# Esquema.net
KiCad netlist of a schematic drawn in EAGLE
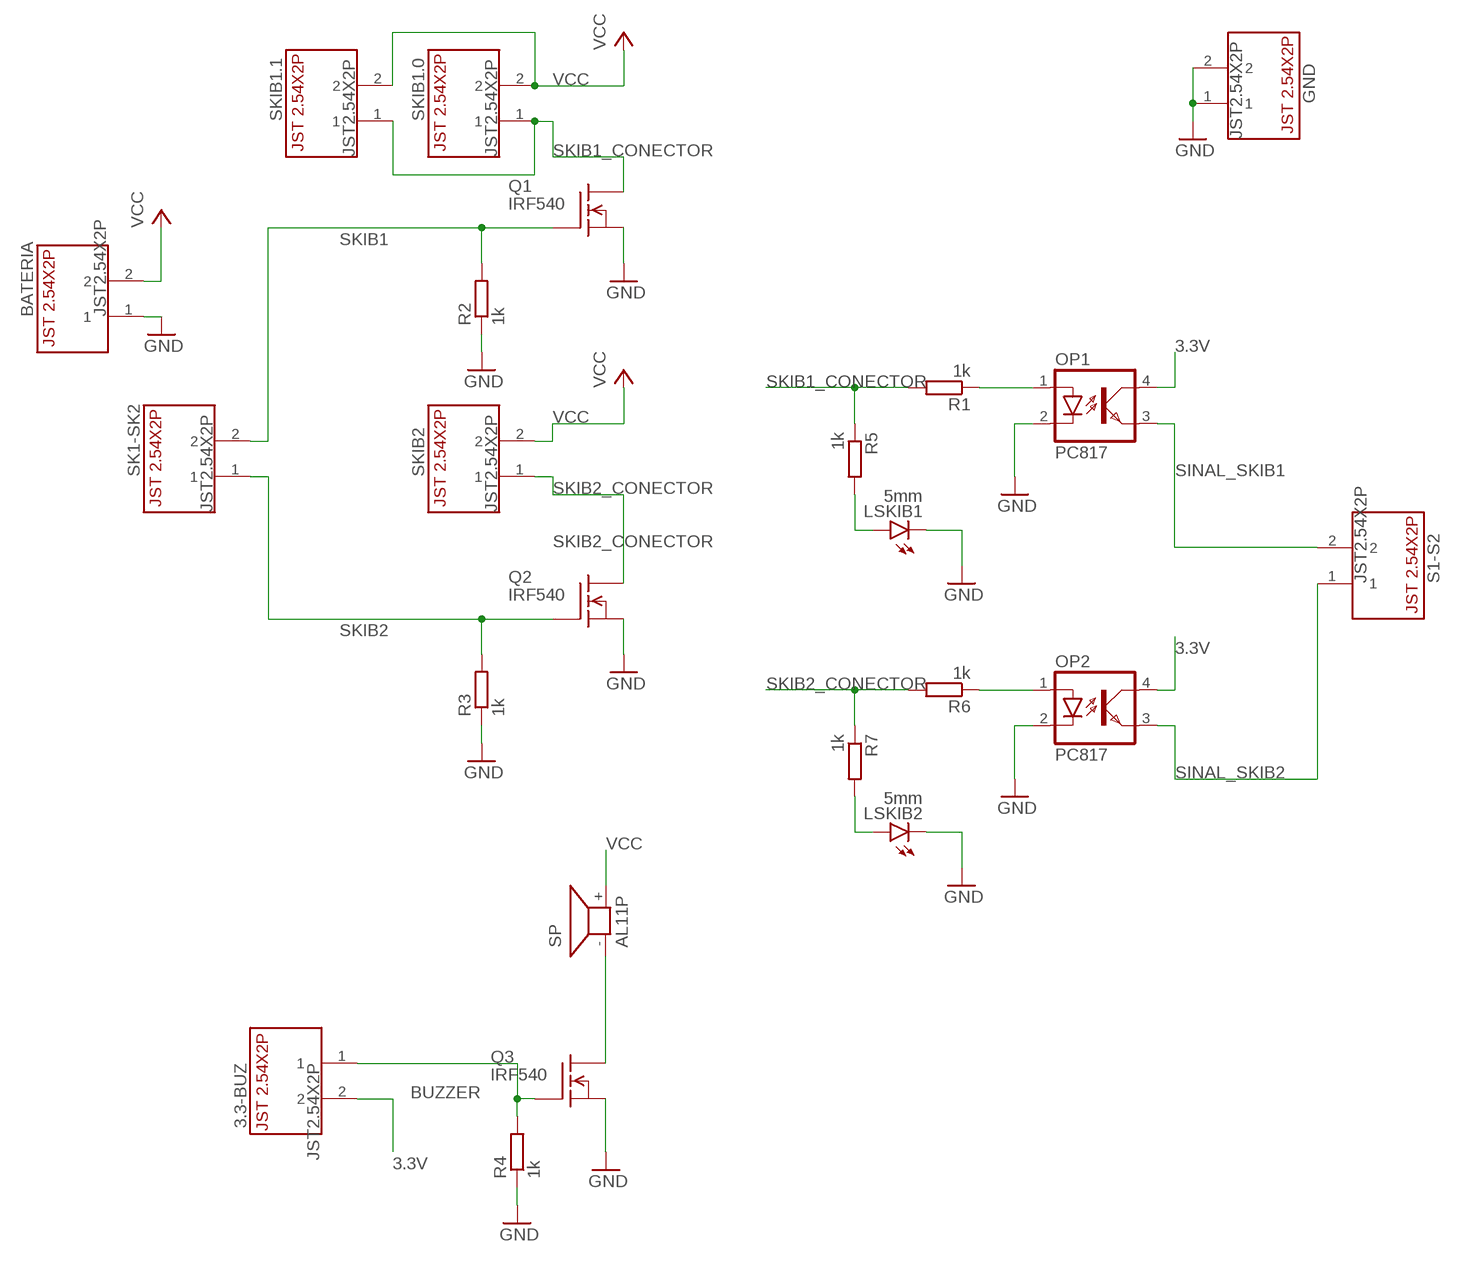
[diagram p0: schematic, sheet 1]

(export (version "E")
  (design (tool "Eeschema 10.0.6"))
  (components
    (comp (ref "3.3-BUZ")
      (value "JST2.54X2P")
      (footprint "eagle-import:JST2.54X2P_FOOTPRINT")
      (libsource (lib "eagle-import") (part "JST2.54X2P"))
    )
    (comp (ref "BATERIA")
      (value "JST2.54X2P")
      (footprint "eagle-import:JST2.54X2P_FOOTPRINT")
      (libsource (lib "eagle-import") (part "JST2.54X2P"))
    )
    (comp (ref "GND")
      (value "JST2.54X2P")
      (footprint "eagle-import:JST2.54X2P_FOOTPRINT")
      (libsource (lib "eagle-import") (part "JST2.54X2P"))
    )
    (comp (ref "LSKIB1")
      (value "5mm")
      (footprint "eagle-import:LED5MM")
      (libsource (lib "eagle-import") (part "LED5MM"))
    )
    (comp (ref "LSKIB2")
      (value "5mm")
      (footprint "eagle-import:LED5MM")
      (libsource (lib "eagle-import") (part "LED5MM"))
    )
    (comp (ref "OP1")
      (value "PC817")
      (footprint "eagle-import:DIL04")
      (fields (field (name "MPN") "PC817X4J000F"))
      (libsource (lib "eagle-import") (part "PC817"))
    )
    (comp (ref "OP2")
      (value "PC817")
      (footprint "eagle-import:DIL04")
      (fields (field (name "MPN") "PC817X4J000F"))
      (libsource (lib "eagle-import") (part "PC817"))
    )
    (comp (ref "Q1")
      (value "IRF540")
      (footprint "eagle-import:TO220")
      (libsource (lib "eagle-import") (part "IRF540"))
    )
    (comp (ref "Q2")
      (value "IRF540")
      (footprint "eagle-import:TO220")
      (libsource (lib "eagle-import") (part "IRF540"))
    )
    (comp (ref "Q3")
      (value "IRF540")
      (footprint "eagle-import:TO220")
      (libsource (lib "eagle-import") (part "IRF540"))
    )
    (comp (ref "R1")
      (value "1k")
      (footprint "eagle-import:0207_10")
      (libsource (lib "eagle-import") (part "R-EU_0207/10"))
    )
    (comp (ref "R2")
      (value "1k")
      (footprint "eagle-import:0207_10")
      (libsource (lib "eagle-import") (part "R-EU_0207/10"))
    )
    (comp (ref "R3")
      (value "1k")
      (footprint "eagle-import:0207_10")
      (libsource (lib "eagle-import") (part "R-EU_0207/10"))
    )
    (comp (ref "R4")
      (value "1k")
      (footprint "eagle-import:0207_10")
      (libsource (lib "eagle-import") (part "R-EU_0207/10"))
    )
    (comp (ref "R5")
      (value "1k")
      (footprint "eagle-import:0207_10")
      (libsource (lib "eagle-import") (part "R-EU_0207/10"))
    )
    (comp (ref "R6")
      (value "1k")
      (footprint "eagle-import:0207_10")
      (libsource (lib "eagle-import") (part "R-EU_0207/10"))
    )
    (comp (ref "R7")
      (value "1k")
      (footprint "eagle-import:0207_10")
      (libsource (lib "eagle-import") (part "R-EU_0207/10"))
    )
    (comp (ref "S1-S2")
      (value "JST2.54X2P")
      (footprint "eagle-import:JST2.54X2P_FOOTPRINT")
      (libsource (lib "eagle-import") (part "JST2.54X2P"))
    )
    (comp (ref "SK1-SK2")
      (value "JST2.54X2P")
      (footprint "eagle-import:JST2.54X2P_FOOTPRINT")
      (libsource (lib "eagle-import") (part "JST2.54X2P"))
    )
    (comp (ref "SKIB1.0")
      (value "JST2.54X2P")
      (footprint "eagle-import:JST2.54X2P_FOOTPRINT")
      (libsource (lib "eagle-import") (part "JST2.54X2P"))
    )
    (comp (ref "SKIB1.1")
      (value "JST2.54X2P")
      (footprint "eagle-import:JST2.54X2P_FOOTPRINT")
      (libsource (lib "eagle-import") (part "JST2.54X2P"))
    )
    (comp (ref "SKIB2")
      (value "JST2.54X2P")
      (footprint "eagle-import:JST2.54X2P_FOOTPRINT")
      (libsource (lib "eagle-import") (part "JST2.54X2P"))
    )
    (comp (ref "SP")
      (value "AL11P")
      (footprint "eagle-import:AL11P")
      (libsource (lib "eagle-import") (part "AL11P"))
    )
  )
  (nets
    (net (code "1") (name "/3.3V") (class "Default")
      (node (ref "3.3-BUZ") (pin "2") (pinfunction "2_2") (pintype "bidirectional"))
      (node (ref "OP1") (pin "4") (pinfunction "COL_4") (pintype "passive"))
      (node (ref "OP2") (pin "4") (pinfunction "COL_4") (pintype "passive"))
    )
    (net (code "2") (name "/BUZZER") (class "Default")
      (node (ref "3.3-BUZ") (pin "1") (pinfunction "1_1") (pintype "bidirectional"))
      (node (ref "Q3") (pin "1") (pinfunction "G_1") (pintype "passive"))
      (node (ref "R4") (pin "2") (pinfunction "2_2") (pintype "passive"))
    )
    (net (code "3") (name "/SINAL_SKIB1") (class "Default")
      (node (ref "OP1") (pin "3") (pinfunction "EMIT_3") (pintype "passive"))
      (node (ref "S1-S2") (pin "2") (pinfunction "2_2") (pintype "bidirectional"))
    )
    (net (code "4") (name "/SINAL_SKIB2") (class "Default")
      (node (ref "OP2") (pin "3") (pinfunction "EMIT_3") (pintype "passive"))
      (node (ref "S1-S2") (pin "1") (pinfunction "1_1") (pintype "bidirectional"))
    )
    (net (code "5") (name "/SKIB1") (class "Default")
      (node (ref "Q1") (pin "1") (pinfunction "G_1") (pintype "passive"))
      (node (ref "R2") (pin "2") (pinfunction "2_2") (pintype "passive"))
      (node (ref "SK1-SK2") (pin "2") (pinfunction "2_2") (pintype "bidirectional"))
    )
    (net (code "6") (name "/SKIB1_CONECTOR") (class "Default")
      (node (ref "Q1") (pin "2") (pinfunction "D_2") (pintype "passive"))
      (node (ref "R1") (pin "2") (pinfunction "2_2") (pintype "passive"))
      (node (ref "R5") (pin "1") (pinfunction "1_1") (pintype "passive"))
      (node (ref "SKIB1.0") (pin "1") (pinfunction "1_1") (pintype "bidirectional"))
      (node (ref "SKIB1.1") (pin "1") (pinfunction "1_1") (pintype "bidirectional"))
    )
    (net (code "7") (name "/SKIB2") (class "Default")
      (node (ref "Q2") (pin "1") (pinfunction "G_1") (pintype "passive"))
      (node (ref "R3") (pin "2") (pinfunction "2_2") (pintype "passive"))
      (node (ref "SK1-SK2") (pin "1") (pinfunction "1_1") (pintype "bidirectional"))
    )
    (net (code "8") (name "/SKIB2_CONECTOR") (class "Default")
      (node (ref "Q2") (pin "2") (pinfunction "D_2") (pintype "passive"))
      (node (ref "R6") (pin "2") (pinfunction "2_2") (pintype "passive"))
      (node (ref "R7") (pin "1") (pinfunction "1_1") (pintype "passive"))
      (node (ref "SKIB2") (pin "1") (pinfunction "1_1") (pintype "bidirectional"))
    )
    (net (code "9") (name "GND") (class "Default")
      (node (ref "BATERIA") (pin "1") (pinfunction "1_1") (pintype "bidirectional"))
      (node (ref "GND") (pin "1") (pinfunction "1_1") (pintype "bidirectional"))
      (node (ref "GND") (pin "2") (pinfunction "2_2") (pintype "bidirectional"))
      (node (ref "LSKIB1") (pin "K") (pinfunction "C_K") (pintype "passive"))
      (node (ref "LSKIB2") (pin "K") (pinfunction "C_K") (pintype "passive"))
      (node (ref "OP1") (pin "2") (pinfunction "C_2") (pintype "passive"))
      (node (ref "OP2") (pin "2") (pinfunction "C_2") (pintype "passive"))
      (node (ref "Q1") (pin "3") (pinfunction "S_3") (pintype "passive"))
      (node (ref "Q2") (pin "3") (pinfunction "S_3") (pintype "passive"))
      (node (ref "Q3") (pin "3") (pinfunction "S_3") (pintype "passive"))
      (node (ref "R2") (pin "1") (pinfunction "1_1") (pintype "passive"))
      (node (ref "R3") (pin "1") (pinfunction "1_1") (pintype "passive"))
      (node (ref "R4") (pin "1") (pinfunction "1_1") (pintype "passive"))
    )
    (net (code "10") (name "Net-(LSKIB1-PadA)") (class "Default")
      (node (ref "LSKIB1") (pin "A") (pinfunction "A_A") (pintype "passive"))
      (node (ref "R5") (pin "2") (pinfunction "2_2") (pintype "passive"))
    )
    (net (code "11") (name "Net-(LSKIB2-PadA)") (class "Default")
      (node (ref "LSKIB2") (pin "A") (pinfunction "A_A") (pintype "passive"))
      (node (ref "R7") (pin "2") (pinfunction "2_2") (pintype "passive"))
    )
    (net (code "12") (name "Net-(OP1-A)") (class "Default")
      (node (ref "OP1") (pin "1") (pinfunction "A_1") (pintype "passive"))
      (node (ref "R1") (pin "1") (pinfunction "1_1") (pintype "passive"))
    )
    (net (code "13") (name "Net-(OP2-A)") (class "Default")
      (node (ref "OP2") (pin "1") (pinfunction "A_1") (pintype "passive"))
      (node (ref "R6") (pin "1") (pinfunction "1_1") (pintype "passive"))
    )
    (net (code "14") (name "Net-(Q3-D)") (class "Default")
      (node (ref "Q3") (pin "2") (pinfunction "D_2") (pintype "passive"))
      (node (ref "SP") (pin "-") (pinfunction "1_-") (pintype "passive"))
    )
    (net (code "15") (name "VCC") (class "Default")
      (node (ref "BATERIA") (pin "2") (pinfunction "2_2") (pintype "bidirectional"))
      (node (ref "SKIB1.0") (pin "2") (pinfunction "2_2") (pintype "bidirectional"))
      (node (ref "SKIB1.1") (pin "2") (pinfunction "2_2") (pintype "bidirectional"))
      (node (ref "SKIB2") (pin "2") (pinfunction "2_2") (pintype "bidirectional"))
      (node (ref "SP") (pin "+") (pinfunction "2_+") (pintype "passive"))
    )
  )
)
